# Felderblock6-a-1.net
KiCad netlist of a schematic drawn in EAGLE
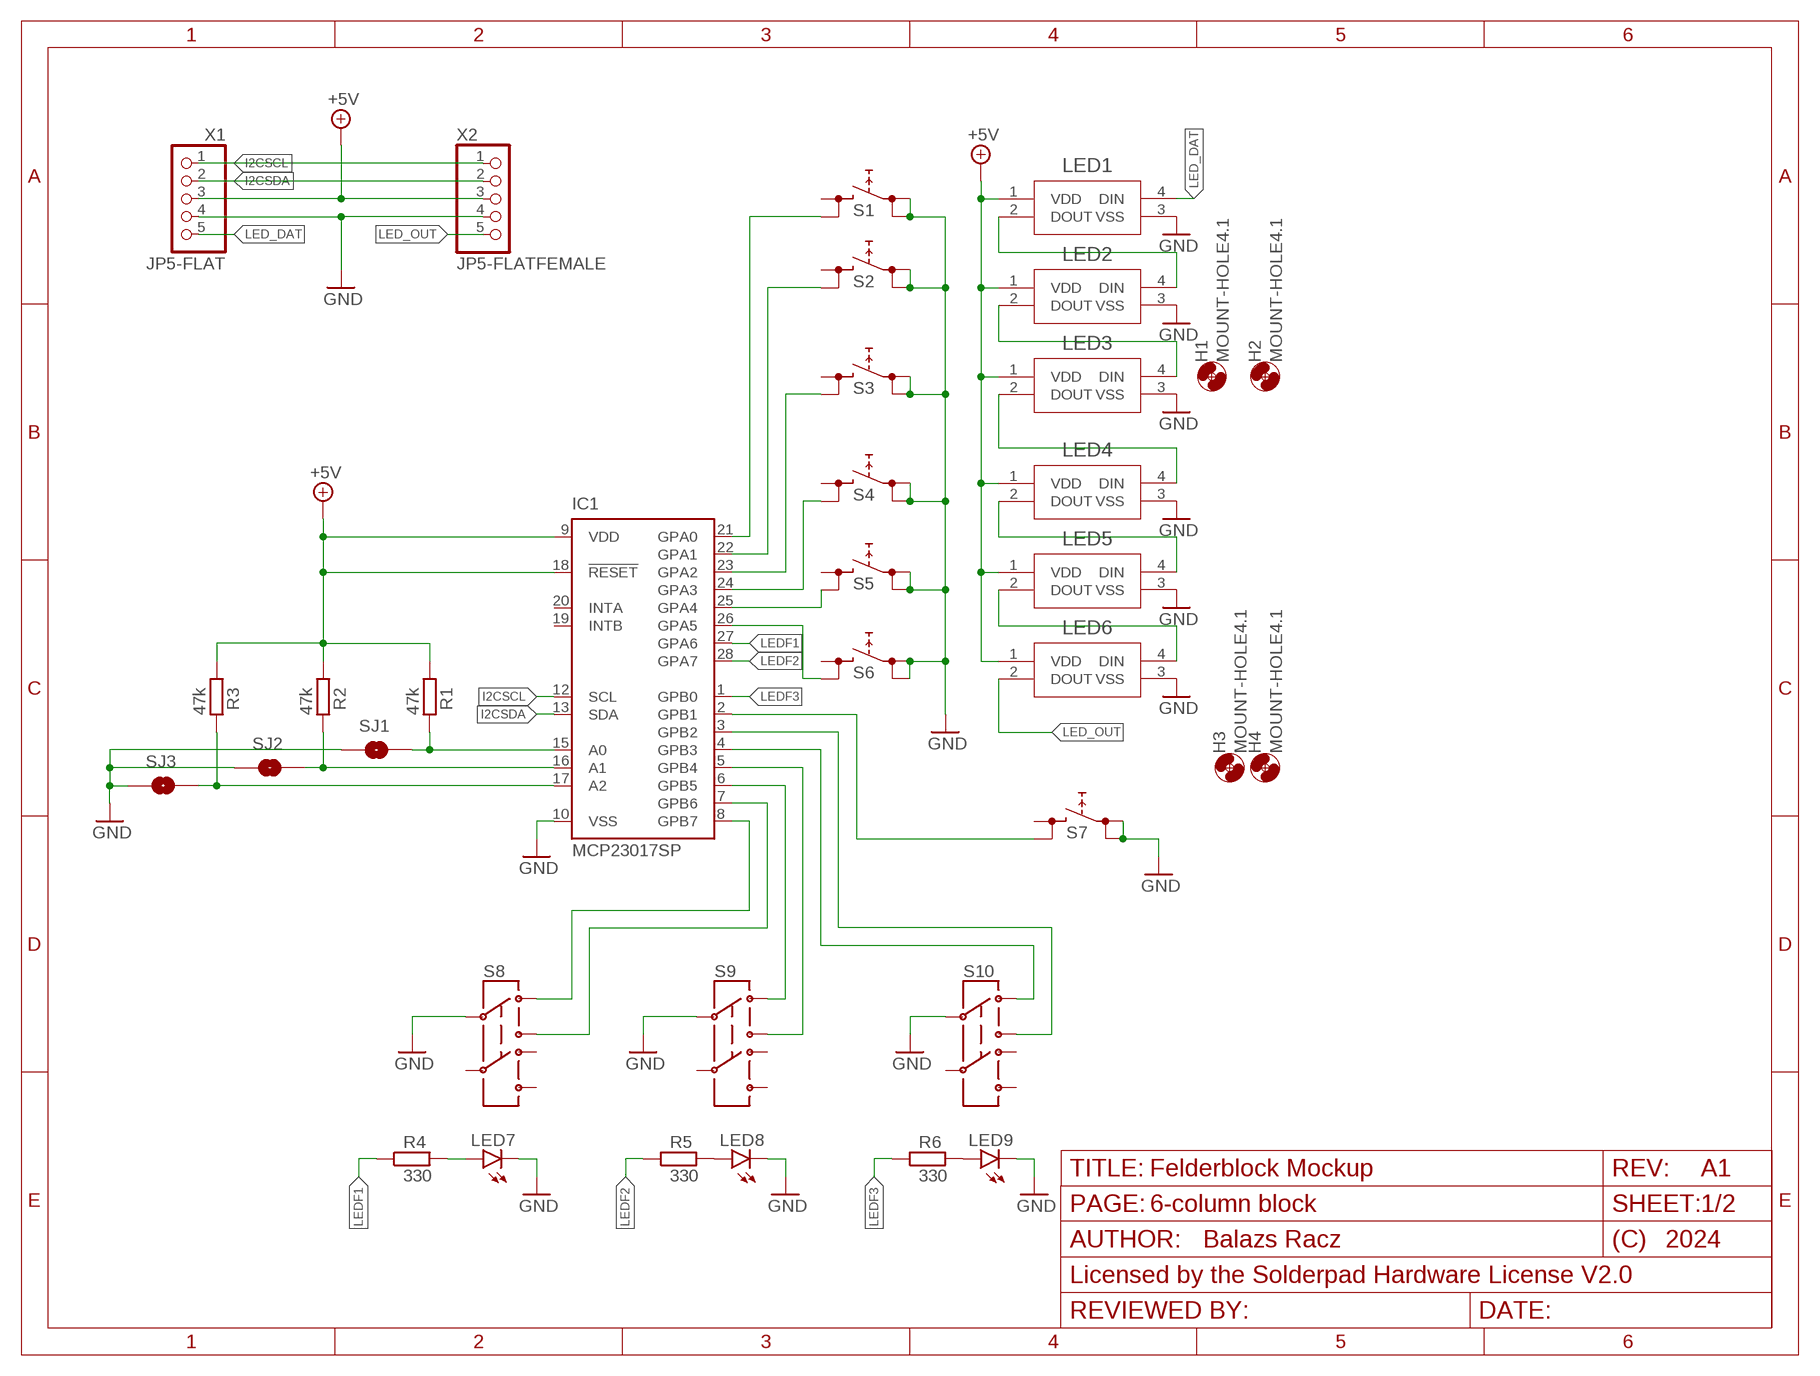
[diagram p0: schematic, sheet 1]

(export (version "E")
  (design (tool "Eeschema 10.0.6"))
  (components
    (comp (ref "H1")
      (value "MOUNT-HOLE4.1")
      (footprint "eagle-import:4,1")
      (libsource (lib "eagle-import") (part "MOUNT-HOLE4.1"))
    )
    (comp (ref "H2")
      (value "MOUNT-HOLE4.1")
      (footprint "eagle-import:4,1")
      (libsource (lib "eagle-import") (part "MOUNT-HOLE4.1"))
    )
    (comp (ref "H3")
      (value "MOUNT-HOLE4.1")
      (footprint "eagle-import:4,1")
      (libsource (lib "eagle-import") (part "MOUNT-HOLE4.1"))
    )
    (comp (ref "H4")
      (value "MOUNT-HOLE4.1")
      (footprint "eagle-import:4,1")
      (libsource (lib "eagle-import") (part "MOUNT-HOLE4.1"))
    )
    (comp (ref "IC1")
      (value "MCP23017SP")
      (footprint "eagle-import:DIL28-3")
      (fields (field (name "MF") "MICROCHIP") (field (name "MPN") "MCP23017-E/SP"))
      (libsource (lib "eagle-import") (part "MCP23017SP"))
    )
    (comp (ref "LED1")
      (value "LED-2812BCOM-16347_SPK-M")
      (footprint "eagle-import:COM-16347_SPK-M")
      (fields
        (field (name "MANUFACTURER_PART_NUMBER") "COM-16347")
        (field (name "COPYRIGHT") "Copyright (C) 2024 Ultra Librarian. All rights reserved.")
      )
      (libsource (lib "eagle-import") (part "LED-2812BCOM-16347_SPK-M"))
    )
    (comp (ref "LED2")
      (value "LED-2812BCOM-16347_SPK-M")
      (footprint "eagle-import:COM-16347_SPK-M")
      (fields
        (field (name "MANUFACTURER_PART_NUMBER") "COM-16347")
        (field (name "COPYRIGHT") "Copyright (C) 2024 Ultra Librarian. All rights reserved.")
      )
      (libsource (lib "eagle-import") (part "LED-2812BCOM-16347_SPK-M"))
    )
    (comp (ref "LED3")
      (value "LED-2812BCOM-16347_SPK-M")
      (footprint "eagle-import:COM-16347_SPK-M")
      (fields
        (field (name "MANUFACTURER_PART_NUMBER") "COM-16347")
        (field (name "COPYRIGHT") "Copyright (C) 2024 Ultra Librarian. All rights reserved.")
      )
      (libsource (lib "eagle-import") (part "LED-2812BCOM-16347_SPK-M"))
    )
    (comp (ref "LED4")
      (value "LED-2812BCOM-16347_SPK-M")
      (footprint "eagle-import:COM-16347_SPK-M")
      (fields
        (field (name "MANUFACTURER_PART_NUMBER") "COM-16347")
        (field (name "COPYRIGHT") "Copyright (C) 2024 Ultra Librarian. All rights reserved.")
      )
      (libsource (lib "eagle-import") (part "LED-2812BCOM-16347_SPK-M"))
    )
    (comp (ref "LED5")
      (value "LED-2812BCOM-16347_SPK-M")
      (footprint "eagle-import:COM-16347_SPK-M")
      (fields
        (field (name "MANUFACTURER_PART_NUMBER") "COM-16347")
        (field (name "COPYRIGHT") "Copyright (C) 2024 Ultra Librarian. All rights reserved.")
      )
      (libsource (lib "eagle-import") (part "LED-2812BCOM-16347_SPK-M"))
    )
    (comp (ref "LED6")
      (value "LED-2812BCOM-16347_SPK-M")
      (footprint "eagle-import:COM-16347_SPK-M")
      (fields
        (field (name "MANUFACTURER_PART_NUMBER") "COM-16347")
        (field (name "COPYRIGHT") "Copyright (C) 2024 Ultra Librarian. All rights reserved.")
      )
      (libsource (lib "eagle-import") (part "LED-2812BCOM-16347_SPK-M"))
    )
    (comp (ref "LED7")
      (value "LEDCHIPLED_0805")
      (footprint "eagle-import:CHIPLED_0805")
      (libsource (lib "eagle-import") (part "LEDCHIPLED_0805"))
    )
    (comp (ref "LED8")
      (value "LEDCHIPLED_0805")
      (footprint "eagle-import:CHIPLED_0805")
      (libsource (lib "eagle-import") (part "LEDCHIPLED_0805"))
    )
    (comp (ref "LED9")
      (value "LEDCHIPLED_0805")
      (footprint "eagle-import:CHIPLED_0805")
      (libsource (lib "eagle-import") (part "LEDCHIPLED_0805"))
    )
    (comp (ref "R1")
      (value "47k")
      (footprint "eagle-import:R0805")
      (libsource (lib "eagle-import") (part "R-EU_R0805"))
    )
    (comp (ref "R2")
      (value "47k")
      (footprint "eagle-import:R0805")
      (libsource (lib "eagle-import") (part "R-EU_R0805"))
    )
    (comp (ref "R3")
      (value "47k")
      (footprint "eagle-import:R0805")
      (libsource (lib "eagle-import") (part "R-EU_R0805"))
    )
    (comp (ref "R4")
      (value "330")
      (footprint "eagle-import:R0805")
      (libsource (lib "eagle-import") (part "R-EU_R0805"))
    )
    (comp (ref "R5")
      (value "330")
      (footprint "eagle-import:R0805")
      (libsource (lib "eagle-import") (part "R-EU_R0805"))
    )
    (comp (ref "R6")
      (value "330")
      (footprint "eagle-import:R0805")
      (libsource (lib "eagle-import") (part "R-EU_R0805"))
    )
    (comp (ref "S1")
      (value "W1")
      (footprint "eagle-import:TACTSW-6X6")
      (libsource (lib "eagle-import") (part "TACTSW-6X6S"))
    )
    (comp (ref "S2")
      (value "W1")
      (footprint "eagle-import:TACTSW-6X6")
      (libsource (lib "eagle-import") (part "TACTSW-6X6S"))
    )
    (comp (ref "S3")
      (value "W1")
      (footprint "eagle-import:TACTSW-6X6")
      (libsource (lib "eagle-import") (part "TACTSW-6X6S"))
    )
    (comp (ref "S4")
      (value "W1")
      (footprint "eagle-import:TACTSW-6X6")
      (libsource (lib "eagle-import") (part "TACTSW-6X6S"))
    )
    (comp (ref "S5")
      (value "W1")
      (footprint "eagle-import:TACTSW-6X6")
      (libsource (lib "eagle-import") (part "TACTSW-6X6S"))
    )
    (comp (ref "S6")
      (value "W1")
      (footprint "eagle-import:TACTSW-6X6")
      (libsource (lib "eagle-import") (part "TACTSW-6X6S"))
    )
    (comp (ref "S7")
      (value "W1")
      (footprint "eagle-import:TACTSW-6X6")
      (libsource (lib "eagle-import") (part "TACTSW-6X6S"))
    )
    (comp (ref "S8")
      (value "SWITCH-DPDT")
      (footprint "eagle-import:DP-T1")
      (libsource (lib "eagle-import") (part "SWITCH-DPDT"))
    )
    (comp (ref "S9")
      (value "SWITCH-DPDT")
      (footprint "eagle-import:DP-T1")
      (libsource (lib "eagle-import") (part "SWITCH-DPDT"))
    )
    (comp (ref "S10")
      (value "SWITCH-DPDT")
      (footprint "eagle-import:DP-T1")
      (libsource (lib "eagle-import") (part "SWITCH-DPDT"))
    )
    (comp (ref "SJ1")
      (value "SJRND2")
      (footprint "eagle-import:SJ_RND2")
      (libsource (lib "eagle-import") (part "SJRND2"))
    )
    (comp (ref "SJ2")
      (value "SJRND2")
      (footprint "eagle-import:SJ_RND2")
      (libsource (lib "eagle-import") (part "SJRND2"))
    )
    (comp (ref "SJ3")
      (value "SJRND2")
      (footprint "eagle-import:SJ_RND2")
      (libsource (lib "eagle-import") (part "SJRND2"))
    )
    (comp (ref "X1")
      (value "JP5-FLAT")
      (footprint "eagle-import:JP5F")
      (libsource (lib "eagle-import") (part "JP5-FLAT"))
    )
    (comp (ref "X2")
      (value "JP5-FLATFEMALE")
      (footprint "eagle-import:JP5F-FEM")
      (libsource (lib "eagle-import") (part "JP5-FLATFEMALE"))
    )
  )
  (nets
    (net (code "1") (name "+5V") (class "Default")
      (node (ref "IC1") (pin "18") (pinfunction "~{RESET}_18") (pintype "input"))
      (node (ref "IC1") (pin "9") (pinfunction "VDD_9") (pintype "power_in"))
      (node (ref "LED1") (pin "1") (pinfunction "VDD_1") (pintype "power_in"))
      (node (ref "LED2") (pin "1") (pinfunction "VDD_1") (pintype "power_in"))
      (node (ref "LED3") (pin "1") (pinfunction "VDD_1") (pintype "power_in"))
      (node (ref "LED4") (pin "1") (pinfunction "VDD_1") (pintype "power_in"))
      (node (ref "LED5") (pin "1") (pinfunction "VDD_1") (pintype "power_in"))
      (node (ref "LED6") (pin "1") (pinfunction "VDD_1") (pintype "power_in"))
      (node (ref "R1") (pin "1") (pinfunction "1_1") (pintype "passive"))
      (node (ref "R2") (pin "1") (pinfunction "1_1") (pintype "passive"))
      (node (ref "R3") (pin "1") (pinfunction "1_1") (pintype "passive"))
      (node (ref "X1") (pin "3") (pinfunction "3_3") (pintype "passive"))
      (node (ref "X2") (pin "3") (pinfunction "3_3") (pintype "passive"))
    )
    (net (code "2") (name "GND") (class "Default")
      (node (ref "IC1") (pin "10") (pinfunction "VSS_10") (pintype "power_in"))
      (node (ref "LED1") (pin "3") (pinfunction "VSS_3") (pintype "passive"))
      (node (ref "LED2") (pin "3") (pinfunction "VSS_3") (pintype "passive"))
      (node (ref "LED3") (pin "3") (pinfunction "VSS_3") (pintype "passive"))
      (node (ref "LED4") (pin "3") (pinfunction "VSS_3") (pintype "passive"))
      (node (ref "LED5") (pin "3") (pinfunction "VSS_3") (pintype "passive"))
      (node (ref "LED6") (pin "3") (pinfunction "VSS_3") (pintype "passive"))
      (node (ref "LED7") (pin "C") (pinfunction "C_C") (pintype "passive"))
      (node (ref "LED8") (pin "C") (pinfunction "C_C") (pintype "passive"))
      (node (ref "LED9") (pin "C") (pinfunction "C_C") (pintype "passive"))
      (node (ref "S1") (pin "1") (pinfunction "1.1_1") (pintype "passive"))
      (node (ref "S1") (pin "2") (pinfunction "1.2_2") (pintype "passive"))
      (node (ref "S10") (pin "2") (pinfunction "1C_2") (pintype "bidirectional"))
      (node (ref "S2") (pin "1") (pinfunction "1.1_1") (pintype "passive"))
      (node (ref "S2") (pin "2") (pinfunction "1.2_2") (pintype "passive"))
      (node (ref "S3") (pin "1") (pinfunction "1.1_1") (pintype "passive"))
      (node (ref "S3") (pin "2") (pinfunction "1.2_2") (pintype "passive"))
      (node (ref "S4") (pin "1") (pinfunction "1.1_1") (pintype "passive"))
      (node (ref "S4") (pin "2") (pinfunction "1.2_2") (pintype "passive"))
      (node (ref "S5") (pin "1") (pinfunction "1.1_1") (pintype "passive"))
      (node (ref "S5") (pin "2") (pinfunction "1.2_2") (pintype "passive"))
      (node (ref "S6") (pin "1") (pinfunction "1.1_1") (pintype "passive"))
      (node (ref "S6") (pin "2") (pinfunction "1.2_2") (pintype "passive"))
      (node (ref "S7") (pin "1") (pinfunction "1.1_1") (pintype "passive"))
      (node (ref "S7") (pin "2") (pinfunction "1.2_2") (pintype "passive"))
      (node (ref "S8") (pin "2") (pinfunction "1C_2") (pintype "bidirectional"))
      (node (ref "S9") (pin "2") (pinfunction "1C_2") (pintype "bidirectional"))
      (node (ref "SJ1") (pin "P$1") (pinfunction "1_P$1") (pintype "passive"))
      (node (ref "SJ2") (pin "P$1") (pinfunction "1_P$1") (pintype "passive"))
      (node (ref "SJ3") (pin "P$1") (pinfunction "1_P$1") (pintype "passive"))
      (node (ref "X1") (pin "4") (pinfunction "4_4") (pintype "passive"))
      (node (ref "X2") (pin "4") (pinfunction "4_4") (pintype "passive"))
    )
    (net (code "3") (name "I2CSCL") (class "Default")
      (node (ref "IC1") (pin "12") (pinfunction "SCL_12") (pintype "input"))
      (node (ref "X1") (pin "1") (pinfunction "1_1") (pintype "passive"))
      (node (ref "X2") (pin "1") (pinfunction "1_1") (pintype "passive"))
    )
    (net (code "4") (name "I2CSDA") (class "Default")
      (node (ref "IC1") (pin "13") (pinfunction "SDA_13") (pintype "bidirectional"))
      (node (ref "X1") (pin "2") (pinfunction "2_2") (pintype "passive"))
      (node (ref "X2") (pin "2") (pinfunction "2_2") (pintype "passive"))
    )
    (net (code "5") (name "LEDF1") (class "Default")
      (node (ref "IC1") (pin "27") (pinfunction "GPA6_27") (pintype "bidirectional"))
      (node (ref "R4") (pin "1") (pinfunction "1_1") (pintype "passive"))
    )
    (net (code "6") (name "LEDF2") (class "Default")
      (node (ref "IC1") (pin "28") (pinfunction "GPA7_28") (pintype "bidirectional"))
      (node (ref "R5") (pin "1") (pinfunction "1_1") (pintype "passive"))
    )
    (net (code "7") (name "LEDF3") (class "Default")
      (node (ref "IC1") (pin "1") (pinfunction "GPB0_1") (pintype "bidirectional"))
      (node (ref "R6") (pin "1") (pinfunction "1_1") (pintype "passive"))
    )
    (net (code "8") (name "LED_DAT") (class "Default")
      (node (ref "LED1") (pin "4") (pinfunction "DIN_4") (pintype "input"))
      (node (ref "X1") (pin "5") (pinfunction "5_5") (pintype "passive"))
    )
    (net (code "9") (name "LED_OUT") (class "Default")
      (node (ref "LED6") (pin "2") (pinfunction "DOUT_2") (pintype "output"))
      (node (ref "X2") (pin "5") (pinfunction "5_5") (pintype "passive"))
    )
    (net (code "10") (name "Net-(IC1-A0)") (class "Default")
      (node (ref "IC1") (pin "15") (pinfunction "A0_15") (pintype "input"))
      (node (ref "R1") (pin "2") (pinfunction "2_2") (pintype "passive"))
      (node (ref "SJ1") (pin "P$2") (pinfunction "2_P$2") (pintype "passive"))
    )
    (net (code "11") (name "Net-(IC1-A1)") (class "Default")
      (node (ref "IC1") (pin "16") (pinfunction "A1_16") (pintype "input"))
      (node (ref "R2") (pin "2") (pinfunction "2_2") (pintype "passive"))
      (node (ref "SJ2") (pin "P$2") (pinfunction "2_P$2") (pintype "passive"))
    )
    (net (code "12") (name "Net-(IC1-A2)") (class "Default")
      (node (ref "IC1") (pin "17") (pinfunction "A2_17") (pintype "input"))
      (node (ref "R3") (pin "2") (pinfunction "2_2") (pintype "passive"))
      (node (ref "SJ3") (pin "P$2") (pinfunction "2_P$2") (pintype "passive"))
    )
    (net (code "13") (name "Net-(IC1-GPA0)") (class "Default")
      (node (ref "IC1") (pin "21") (pinfunction "GPA0_21") (pintype "bidirectional"))
      (node (ref "S1") (pin "4") (pinfunction "2.2_4") (pintype "passive"))
    )
    (net (code "14") (name "Net-(IC1-GPA1)") (class "Default")
      (node (ref "IC1") (pin "22") (pinfunction "GPA1_22") (pintype "bidirectional"))
      (node (ref "S2") (pin "4") (pinfunction "2.2_4") (pintype "passive"))
    )
    (net (code "15") (name "Net-(IC1-GPA2)") (class "Default")
      (node (ref "IC1") (pin "23") (pinfunction "GPA2_23") (pintype "bidirectional"))
      (node (ref "S3") (pin "4") (pinfunction "2.2_4") (pintype "passive"))
    )
    (net (code "16") (name "Net-(IC1-GPA3)") (class "Default")
      (node (ref "IC1") (pin "24") (pinfunction "GPA3_24") (pintype "bidirectional"))
      (node (ref "S4") (pin "4") (pinfunction "2.2_4") (pintype "passive"))
    )
    (net (code "17") (name "Net-(IC1-GPA4)") (class "Default")
      (node (ref "IC1") (pin "25") (pinfunction "GPA4_25") (pintype "bidirectional"))
      (node (ref "S5") (pin "4") (pinfunction "2.2_4") (pintype "passive"))
    )
    (net (code "18") (name "Net-(IC1-GPA5)") (class "Default")
      (node (ref "IC1") (pin "26") (pinfunction "GPA5_26") (pintype "bidirectional"))
      (node (ref "S6") (pin "4") (pinfunction "2.2_4") (pintype "passive"))
    )
    (net (code "19") (name "Net-(IC1-GPB1)") (class "Default")
      (node (ref "IC1") (pin "2") (pinfunction "GPB1_2") (pintype "bidirectional"))
      (node (ref "S7") (pin "4") (pinfunction "2.2_4") (pintype "passive"))
    )
    (net (code "20") (name "Net-(IC1-GPB2)") (class "Default")
      (node (ref "IC1") (pin "3") (pinfunction "GPB2_3") (pintype "bidirectional"))
      (node (ref "S10") (pin "3") (pinfunction "1B_3") (pintype "bidirectional"))
    )
    (net (code "21") (name "Net-(IC1-GPB3)") (class "Default")
      (node (ref "IC1") (pin "4") (pinfunction "GPB3_4") (pintype "bidirectional"))
      (node (ref "S10") (pin "1") (pinfunction "1A_1") (pintype "bidirectional"))
    )
    (net (code "22") (name "Net-(IC1-GPB4)") (class "Default")
      (node (ref "IC1") (pin "5") (pinfunction "GPB4_5") (pintype "bidirectional"))
      (node (ref "S9") (pin "3") (pinfunction "1B_3") (pintype "bidirectional"))
    )
    (net (code "23") (name "Net-(IC1-GPB5)") (class "Default")
      (node (ref "IC1") (pin "6") (pinfunction "GPB5_6") (pintype "bidirectional"))
      (node (ref "S9") (pin "1") (pinfunction "1A_1") (pintype "bidirectional"))
    )
    (net (code "24") (name "Net-(IC1-GPB6)") (class "Default")
      (node (ref "IC1") (pin "7") (pinfunction "GPB6_7") (pintype "bidirectional"))
      (node (ref "S8") (pin "3") (pinfunction "1B_3") (pintype "bidirectional"))
    )
    (net (code "25") (name "Net-(IC1-GPB7)") (class "Default")
      (node (ref "IC1") (pin "8") (pinfunction "GPB7_8") (pintype "bidirectional"))
      (node (ref "S8") (pin "1") (pinfunction "1A_1") (pintype "bidirectional"))
    )
    (net (code "26") (name "Net-(LED1-DOUT)") (class "Default")
      (node (ref "LED1") (pin "2") (pinfunction "DOUT_2") (pintype "output"))
      (node (ref "LED2") (pin "4") (pinfunction "DIN_4") (pintype "input"))
    )
    (net (code "27") (name "Net-(LED2-DOUT)") (class "Default")
      (node (ref "LED2") (pin "2") (pinfunction "DOUT_2") (pintype "output"))
      (node (ref "LED3") (pin "4") (pinfunction "DIN_4") (pintype "input"))
    )
    (net (code "28") (name "Net-(LED3-DOUT)") (class "Default")
      (node (ref "LED3") (pin "2") (pinfunction "DOUT_2") (pintype "output"))
      (node (ref "LED4") (pin "4") (pinfunction "DIN_4") (pintype "input"))
    )
    (net (code "29") (name "Net-(LED4-DOUT)") (class "Default")
      (node (ref "LED4") (pin "2") (pinfunction "DOUT_2") (pintype "output"))
      (node (ref "LED5") (pin "4") (pinfunction "DIN_4") (pintype "input"))
    )
    (net (code "30") (name "Net-(LED5-DOUT)") (class "Default")
      (node (ref "LED5") (pin "2") (pinfunction "DOUT_2") (pintype "output"))
      (node (ref "LED6") (pin "4") (pinfunction "DIN_4") (pintype "input"))
    )
    (net (code "31") (name "Net-(LED7-PadA)") (class "Default")
      (node (ref "LED7") (pin "A") (pinfunction "A_A") (pintype "passive"))
      (node (ref "R4") (pin "2") (pinfunction "2_2") (pintype "passive"))
    )
    (net (code "32") (name "Net-(LED8-PadA)") (class "Default")
      (node (ref "LED8") (pin "A") (pinfunction "A_A") (pintype "passive"))
      (node (ref "R5") (pin "2") (pinfunction "2_2") (pintype "passive"))
    )
    (net (code "33") (name "Net-(LED9-PadA)") (class "Default")
      (node (ref "LED9") (pin "A") (pinfunction "A_A") (pintype "passive"))
      (node (ref "R6") (pin "2") (pinfunction "2_2") (pintype "passive"))
    )
    (net (code "34") (name "unconnected-(IC1-INTA-Pad20)") (class "Default")
      (node (ref "IC1") (pin "20") (pinfunction "INTA_20") (pintype "output"))
    )
    (net (code "35") (name "unconnected-(IC1-INTB-Pad19)") (class "Default")
      (node (ref "IC1") (pin "19") (pinfunction "INTB_19") (pintype "output"))
    )
    (net (code "36") (name "unconnected-(S1-2.1-Pad3)") (class "Default")
      (node (ref "S1") (pin "3") (pinfunction "2.1_3") (pintype "passive"))
    )
    (net (code "37") (name "unconnected-(S2-2.1-Pad3)") (class "Default")
      (node (ref "S2") (pin "3") (pinfunction "2.1_3") (pintype "passive"))
    )
    (net (code "38") (name "unconnected-(S3-2.1-Pad3)") (class "Default")
      (node (ref "S3") (pin "3") (pinfunction "2.1_3") (pintype "passive"))
    )
    (net (code "39") (name "unconnected-(S4-2.1-Pad3)") (class "Default")
      (node (ref "S4") (pin "3") (pinfunction "2.1_3") (pintype "passive"))
    )
    (net (code "40") (name "unconnected-(S5-2.1-Pad3)") (class "Default")
      (node (ref "S5") (pin "3") (pinfunction "2.1_3") (pintype "passive"))
    )
    (net (code "41") (name "unconnected-(S6-2.1-Pad3)") (class "Default")
      (node (ref "S6") (pin "3") (pinfunction "2.1_3") (pintype "passive"))
    )
    (net (code "42") (name "unconnected-(S7-2.1-Pad3)") (class "Default")
      (node (ref "S7") (pin "3") (pinfunction "2.1_3") (pintype "passive"))
    )
    (net (code "43") (name "unconnected-(S8-2A-Pad4)") (class "Default")
      (node (ref "S8") (pin "4") (pinfunction "2A_4") (pintype "bidirectional"))
    )
    (net (code "44") (name "unconnected-(S8-2B-Pad6)") (class "Default")
      (node (ref "S8") (pin "6") (pinfunction "2B_6") (pintype "bidirectional"))
    )
    (net (code "45") (name "unconnected-(S8-2C-Pad5)") (class "Default")
      (node (ref "S8") (pin "5") (pinfunction "2C_5") (pintype "bidirectional"))
    )
    (net (code "46") (name "unconnected-(S9-2A-Pad4)") (class "Default")
      (node (ref "S9") (pin "4") (pinfunction "2A_4") (pintype "bidirectional"))
    )
    (net (code "47") (name "unconnected-(S9-2B-Pad6)") (class "Default")
      (node (ref "S9") (pin "6") (pinfunction "2B_6") (pintype "bidirectional"))
    )
    (net (code "48") (name "unconnected-(S9-2C-Pad5)") (class "Default")
      (node (ref "S9") (pin "5") (pinfunction "2C_5") (pintype "bidirectional"))
    )
    (net (code "49") (name "unconnected-(S10-2A-Pad4)") (class "Default")
      (node (ref "S10") (pin "4") (pinfunction "2A_4") (pintype "bidirectional"))
    )
    (net (code "50") (name "unconnected-(S10-2B-Pad6)") (class "Default")
      (node (ref "S10") (pin "6") (pinfunction "2B_6") (pintype "bidirectional"))
    )
    (net (code "51") (name "unconnected-(S10-2C-Pad5)") (class "Default")
      (node (ref "S10") (pin "5") (pinfunction "2C_5") (pintype "bidirectional"))
    )
  )
)
